# gydrodrive_debugger.net
KiCad netlist of a schematic drawn in Altium Designer
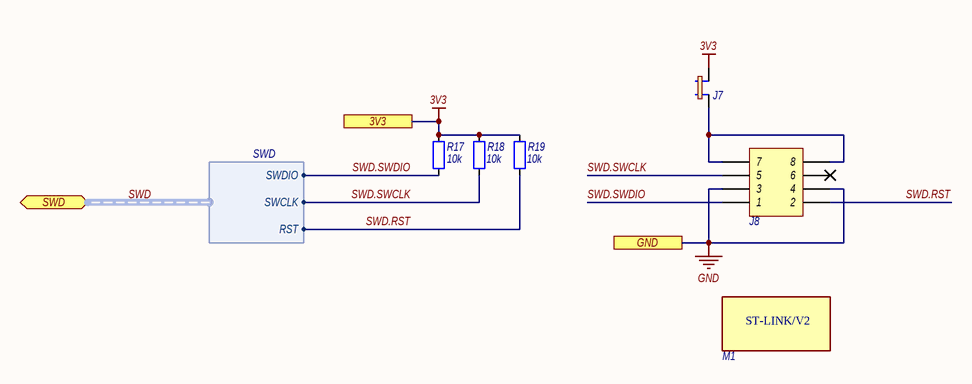
[diagram p0: gydrodrive_debugger.SchDoc]

(export (version "E")
  (design (tool "Eeschema 10.0.6"))
  (components
    (comp (ref "J7")
      (value "PLS-2.54-2 JUMP")
      (footprint "PLS-2-2.54")
      (description "Разъем штыревой шаг 2.54 мм")
      (libsource (lib "StdLib") (part "PIN1x2_JUMP"))
    )
    (comp (ref "J8")
      (value "PBD-2.54-08R")
      (footprint "PBD-8R")
      (description "Разъем")
      (libsource (lib "StdLib") (part "PIN2x4"))
    )
    (comp (ref "M1")
      (value "ST-LINK/V2")
      (footprint "ST_LINK_V2_MINI")
      (description "Программатор")
      (libsource (lib "StdLib") (part "MODULE"))
    )
    (comp (ref "R17")
      (value "RES_0805")
      (footprint "RESC2012-0805M")
      (description "Рез-р, корпус 0805")
      (fields
        (field (name "RESISTANCE") "10k")
        (field (name "PART NUMBER") "RESC_0805")
        (field (name "TOLERANCE") "5%")
      )
      (libsource (lib "StdLib") (part "RES"))
    )
    (comp (ref "R18")
      (value "RES_0805")
      (footprint "RESC2012-0805M")
      (description "Рез-р, корпус 0805")
      (fields
        (field (name "RESISTANCE") "10k")
        (field (name "PART NUMBER") "RESC_0805")
        (field (name "TOLERANCE") "5%")
      )
      (libsource (lib "StdLib") (part "RES"))
    )
    (comp (ref "R19")
      (value "RES_0805")
      (footprint "RESC2012-0805M")
      (description "Рез-р, корпус 0805")
      (fields
        (field (name "RESISTANCE") "10k")
        (field (name "PART NUMBER") "RESC_0805")
        (field (name "TOLERANCE") "5%")
      )
      (libsource (lib "StdLib") (part "RES"))
    )
  )
  (nets
    (net (code "2") (name "/SWD.RST") (class "Default")
      (node (ref "J8") (pin "2") (pinfunction "2_2") (pintype "passive"))
      (node (ref "R19") (pin "1") (pinfunction "1_1") (pintype "passive"))
    )
    (net (code "3") (name "/SWD.SWCLK") (class "Default")
      (node (ref "J8") (pin "5") (pinfunction "5_5") (pintype "passive"))
      (node (ref "R18") (pin "1") (pinfunction "1_1") (pintype "passive"))
    )
    (net (code "4") (name "/SWD.SWDIO") (class "Default")
      (node (ref "J8") (pin "1") (pinfunction "1_1") (pintype "passive"))
      (node (ref "R17") (pin "1") (pinfunction "1_1") (pintype "passive"))
    )
    (net (code "6") (name "3V3") (class "Default")
      (node (ref "J7") (pin "2") (pinfunction "2_2") (pintype "passive"))
      (node (ref "R17") (pin "2") (pinfunction "2_2") (pintype "passive"))
      (node (ref "R18") (pin "2") (pinfunction "2_2") (pintype "passive"))
      (node (ref "R19") (pin "2") (pinfunction "2_2") (pintype "passive"))
    )
    (net (code "7") (name "GND") (class "Default")
      (node (ref "J8") (pin "3") (pinfunction "3_3") (pintype "passive"))
      (node (ref "J8") (pin "4") (pinfunction "4_4") (pintype "passive"))
    )
    (net (code "8") (name "Net-(J7-Pad1)") (class "Default")
      (node (ref "J7") (pin "1") (pinfunction "1_1") (pintype "passive"))
      (node (ref "J8") (pin "7") (pinfunction "7_7") (pintype "passive"))
      (node (ref "J8") (pin "8") (pinfunction "8_8") (pintype "passive"))
    )
    (net (code "9") (name "unconnected-(J8-Pad6)") (class "Default")
      (node (ref "J8") (pin "6") (pinfunction "6_6") (pintype "passive+no_connect"))
    )
  )
)
